# LED_rev3.net
KiCad netlist of a schematic drawn in EAGLE
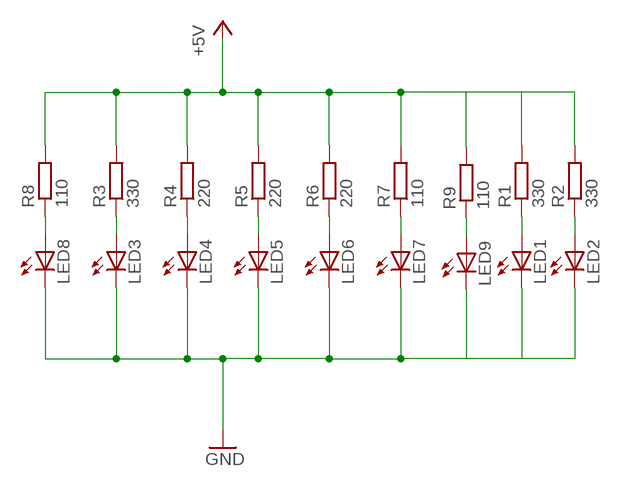
[diagram p0: schematic, sheet 1]

(export (version "E")
  (design (tool "Eeschema 10.0.6"))
  (components
    (comp (ref "LED1")
      (value "LEDCHIPLED_0603")
      (footprint "eagle-import:CHIPLED_0603")
      (libsource (lib "eagle-import") (part "LEDCHIPLED_0603"))
    )
    (comp (ref "LED2")
      (value "LEDCHIPLED_0603")
      (footprint "eagle-import:CHIPLED_0603")
      (libsource (lib "eagle-import") (part "LEDCHIPLED_0603"))
    )
    (comp (ref "LED3")
      (value "LEDCHIPLED_0603")
      (footprint "eagle-import:CHIPLED_0603")
      (libsource (lib "eagle-import") (part "LEDCHIPLED_0603"))
    )
    (comp (ref "LED4")
      (value "LEDCHIPLED_0603")
      (footprint "eagle-import:CHIPLED_0603")
      (libsource (lib "eagle-import") (part "LEDCHIPLED_0603"))
    )
    (comp (ref "LED5")
      (value "LEDCHIPLED_0603")
      (footprint "eagle-import:CHIPLED_0603")
      (libsource (lib "eagle-import") (part "LEDCHIPLED_0603"))
    )
    (comp (ref "LED6")
      (value "LEDCHIPLED_0603")
      (footprint "eagle-import:CHIPLED_0603")
      (libsource (lib "eagle-import") (part "LEDCHIPLED_0603"))
    )
    (comp (ref "LED7")
      (value "LEDCHIPLED_0603")
      (footprint "eagle-import:CHIPLED_0603")
      (libsource (lib "eagle-import") (part "LEDCHIPLED_0603"))
    )
    (comp (ref "LED8")
      (value "LEDCHIPLED_0603")
      (footprint "eagle-import:CHIPLED_0603")
      (libsource (lib "eagle-import") (part "LEDCHIPLED_0603"))
    )
    (comp (ref "LED9")
      (value "LEDCHIPLED_0603")
      (footprint "eagle-import:CHIPLED_0603")
      (libsource (lib "eagle-import") (part "LEDCHIPLED_0603"))
    )
    (comp (ref "R1")
      (value "330")
      (footprint "eagle-import:R0603")
      (libsource (lib "eagle-import") (part "R-EU_R0603"))
    )
    (comp (ref "R2")
      (value "330")
      (footprint "eagle-import:R0603")
      (libsource (lib "eagle-import") (part "R-EU_R0603"))
    )
    (comp (ref "R3")
      (value "330")
      (footprint "eagle-import:R0603")
      (libsource (lib "eagle-import") (part "R-EU_R0603"))
    )
    (comp (ref "R4")
      (value "220")
      (footprint "eagle-import:R0603")
      (libsource (lib "eagle-import") (part "R-EU_R0603"))
    )
    (comp (ref "R5")
      (value "220")
      (footprint "eagle-import:R0603")
      (libsource (lib "eagle-import") (part "R-EU_R0603"))
    )
    (comp (ref "R6")
      (value "220")
      (footprint "eagle-import:R0603")
      (libsource (lib "eagle-import") (part "R-EU_R0603"))
    )
    (comp (ref "R7")
      (value "110")
      (footprint "eagle-import:R0603")
      (libsource (lib "eagle-import") (part "R-EU_R0603"))
    )
    (comp (ref "R8")
      (value "110")
      (footprint "eagle-import:R0603")
      (libsource (lib "eagle-import") (part "R-EU_R0603"))
    )
    (comp (ref "R9")
      (value "110")
      (footprint "eagle-import:R0603")
      (libsource (lib "eagle-import") (part "R-EU_R0603"))
    )
  )
  (nets
    (net (code "1") (name "+5V") (class "Default")
      (node (ref "R1") (pin "2") (pinfunction "2_2") (pintype "passive"))
      (node (ref "R2") (pin "2") (pinfunction "2_2") (pintype "passive"))
      (node (ref "R3") (pin "2") (pinfunction "2_2") (pintype "passive"))
      (node (ref "R4") (pin "2") (pinfunction "2_2") (pintype "passive"))
      (node (ref "R5") (pin "2") (pinfunction "2_2") (pintype "passive"))
      (node (ref "R6") (pin "2") (pinfunction "2_2") (pintype "passive"))
      (node (ref "R7") (pin "2") (pinfunction "2_2") (pintype "passive"))
      (node (ref "R8") (pin "2") (pinfunction "2_2") (pintype "passive"))
      (node (ref "R9") (pin "2") (pinfunction "2_2") (pintype "passive"))
    )
    (net (code "2") (name "GND") (class "Default")
      (node (ref "LED1") (pin "C") (pinfunction "C_C") (pintype "passive"))
      (node (ref "LED2") (pin "C") (pinfunction "C_C") (pintype "passive"))
      (node (ref "LED3") (pin "C") (pinfunction "C_C") (pintype "passive"))
      (node (ref "LED4") (pin "C") (pinfunction "C_C") (pintype "passive"))
      (node (ref "LED5") (pin "C") (pinfunction "C_C") (pintype "passive"))
      (node (ref "LED6") (pin "C") (pinfunction "C_C") (pintype "passive"))
      (node (ref "LED7") (pin "C") (pinfunction "C_C") (pintype "passive"))
      (node (ref "LED8") (pin "C") (pinfunction "C_C") (pintype "passive"))
      (node (ref "LED9") (pin "C") (pinfunction "C_C") (pintype "passive"))
    )
    (net (code "3") (name "Net-(LED1-PadA)") (class "Default")
      (node (ref "LED1") (pin "A") (pinfunction "A_A") (pintype "passive"))
      (node (ref "R1") (pin "1") (pinfunction "1_1") (pintype "passive"))
    )
    (net (code "4") (name "Net-(LED2-PadA)") (class "Default")
      (node (ref "LED2") (pin "A") (pinfunction "A_A") (pintype "passive"))
      (node (ref "R2") (pin "1") (pinfunction "1_1") (pintype "passive"))
    )
    (net (code "5") (name "Net-(LED3-PadA)") (class "Default")
      (node (ref "LED3") (pin "A") (pinfunction "A_A") (pintype "passive"))
      (node (ref "R3") (pin "1") (pinfunction "1_1") (pintype "passive"))
    )
    (net (code "6") (name "Net-(LED4-PadA)") (class "Default")
      (node (ref "LED4") (pin "A") (pinfunction "A_A") (pintype "passive"))
      (node (ref "R4") (pin "1") (pinfunction "1_1") (pintype "passive"))
    )
    (net (code "7") (name "Net-(LED5-PadA)") (class "Default")
      (node (ref "LED5") (pin "A") (pinfunction "A_A") (pintype "passive"))
      (node (ref "R5") (pin "1") (pinfunction "1_1") (pintype "passive"))
    )
    (net (code "8") (name "Net-(LED6-PadA)") (class "Default")
      (node (ref "LED6") (pin "A") (pinfunction "A_A") (pintype "passive"))
      (node (ref "R6") (pin "1") (pinfunction "1_1") (pintype "passive"))
    )
    (net (code "9") (name "Net-(LED7-PadA)") (class "Default")
      (node (ref "LED7") (pin "A") (pinfunction "A_A") (pintype "passive"))
      (node (ref "R7") (pin "1") (pinfunction "1_1") (pintype "passive"))
    )
    (net (code "10") (name "Net-(LED8-PadA)") (class "Default")
      (node (ref "LED8") (pin "A") (pinfunction "A_A") (pintype "passive"))
      (node (ref "R8") (pin "1") (pinfunction "1_1") (pintype "passive"))
    )
    (net (code "11") (name "Net-(LED9-PadA)") (class "Default")
      (node (ref "LED9") (pin "A") (pinfunction "A_A") (pintype "passive"))
      (node (ref "R9") (pin "1") (pinfunction "1_1") (pintype "passive"))
    )
  )
)
